# Example_Project.net
KiCad netlist of a schematic drawn in EAGLE
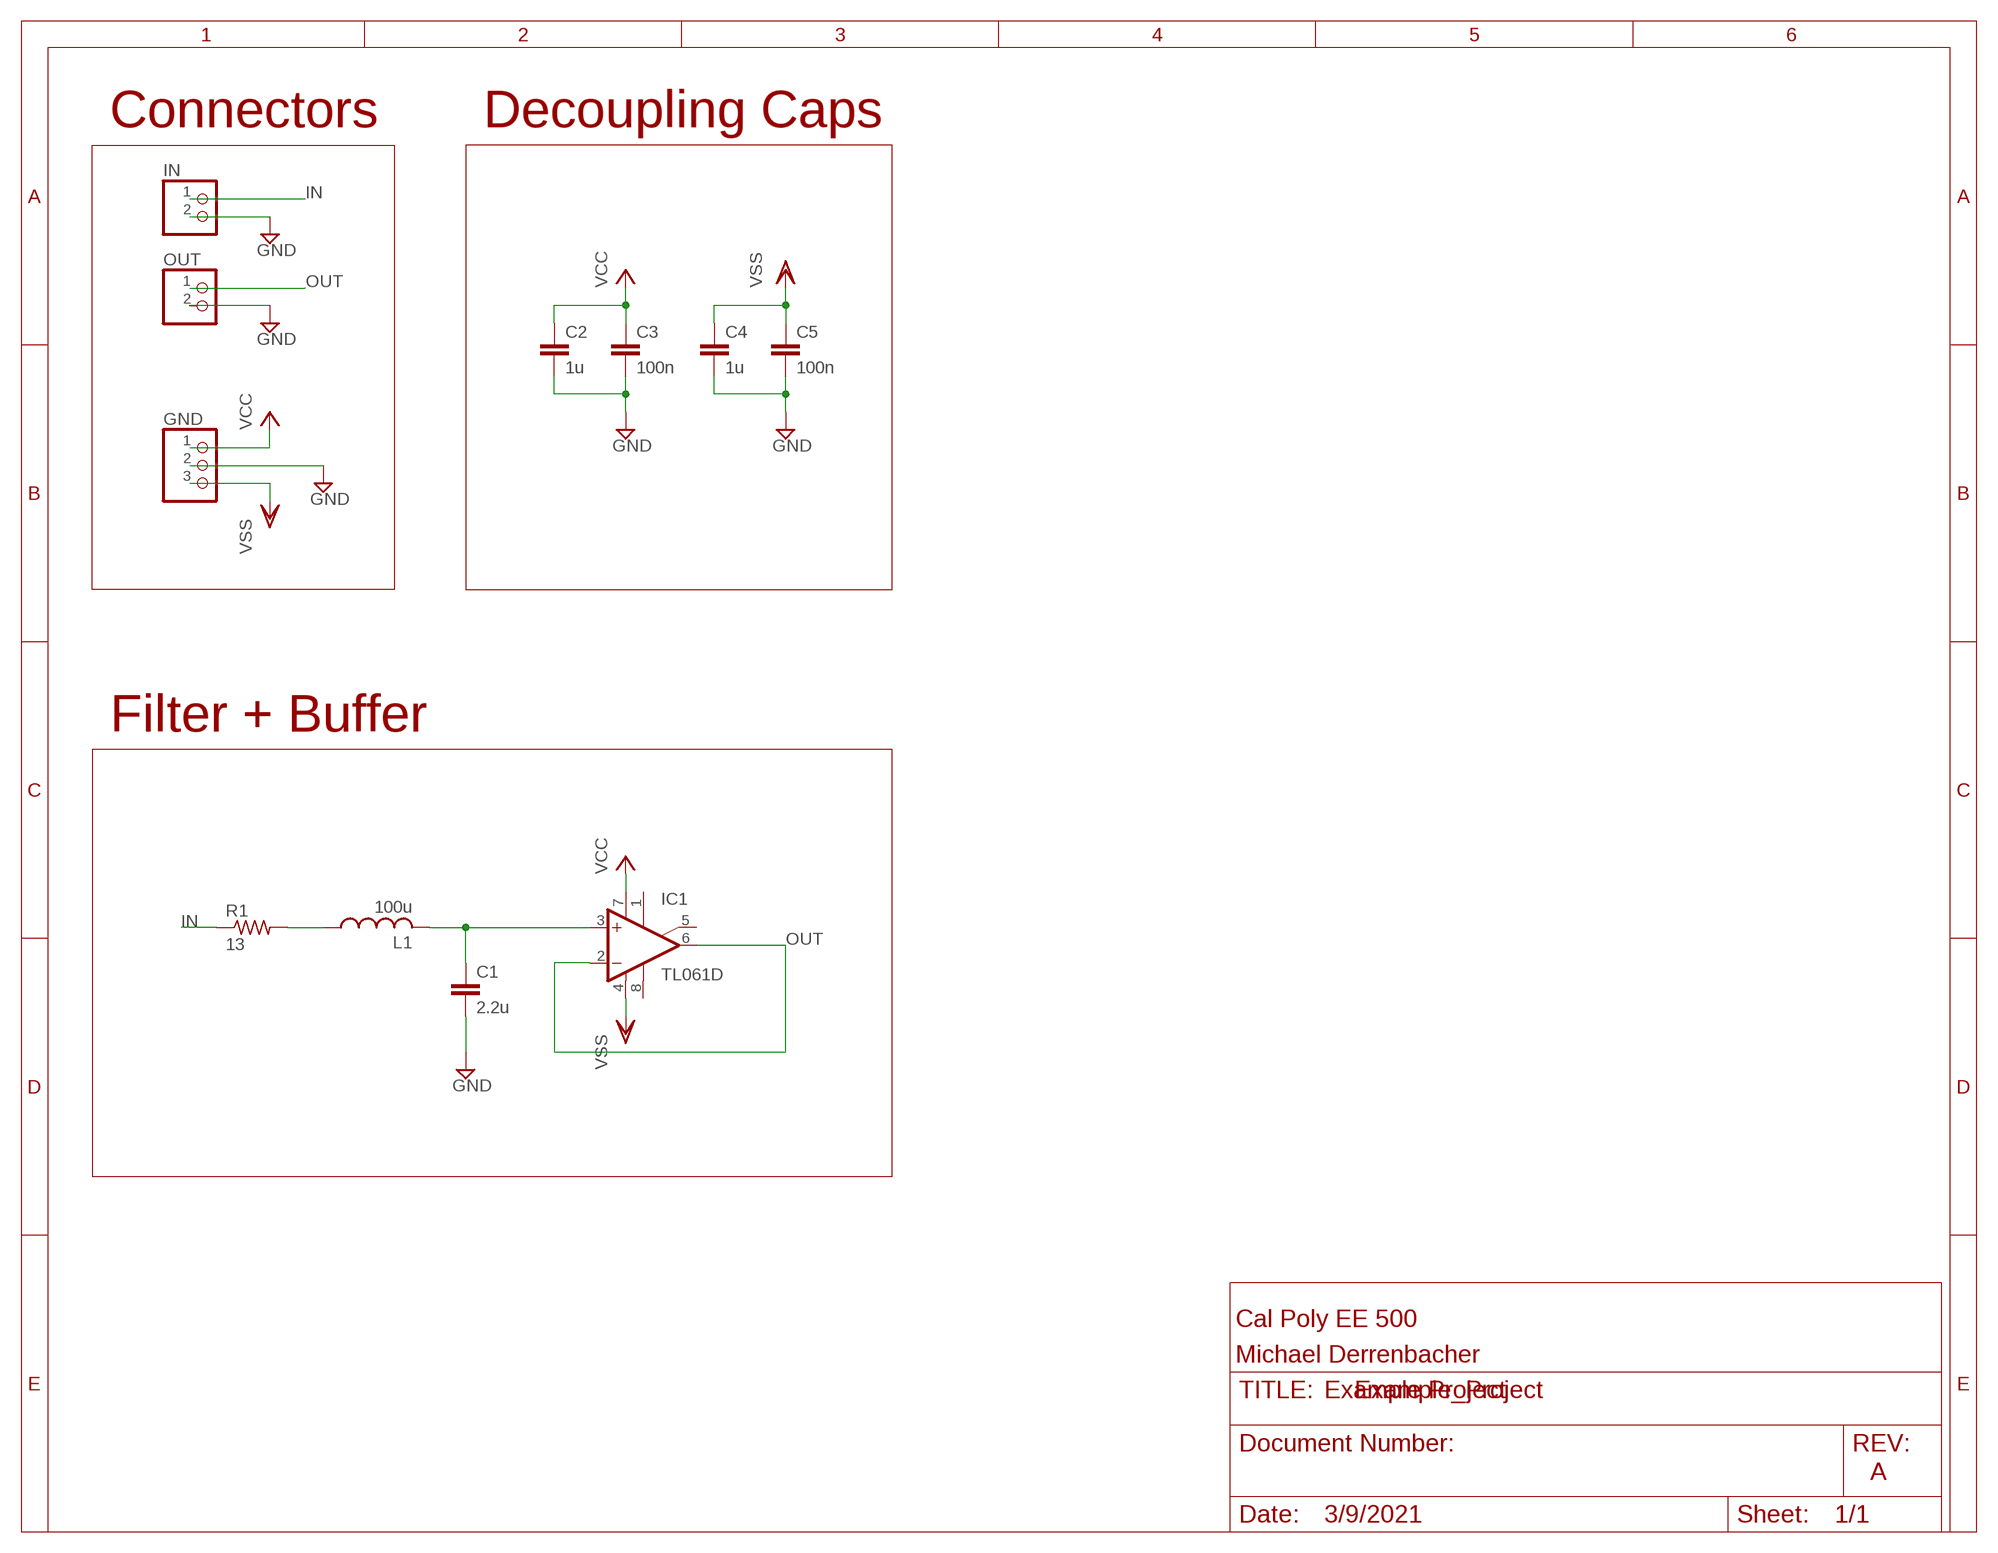
[diagram p0: schematic, sheet 1]

(export (version "E")
  (design (tool "Eeschema 10.0.6"))
  (components
    (comp (ref "C1")
      (value "2.2u")
      (footprint "eagle-import:C0805")
      (libsource (lib "eagle-import") (part "C-EUC0805"))
    )
    (comp (ref "C2")
      (value "1u")
      (footprint "eagle-import:C0805")
      (libsource (lib "eagle-import") (part "C-EUC0805"))
    )
    (comp (ref "C3")
      (value "100n")
      (footprint "eagle-import:C0805")
      (libsource (lib "eagle-import") (part "C-EUC0805"))
    )
    (comp (ref "C4")
      (value "1u")
      (footprint "eagle-import:C0805")
      (libsource (lib "eagle-import") (part "C-EUC0805"))
    )
    (comp (ref "C5")
      (value "100n")
      (footprint "eagle-import:C0805")
      (libsource (lib "eagle-import") (part "C-EUC0805"))
    )
    (comp (ref "GND")
      (value "PINHD-1X3")
      (footprint "eagle-import:1X03")
      (libsource (lib "eagle-import") (part "PINHD-1X3"))
    )
    (comp (ref "IC1")
      (value "TL061D")
      (footprint "eagle-import:SO08")
      (libsource (lib "eagle-import") (part "TL061D"))
    )
    (comp (ref "IN")
      (value "PINHD-1X2")
      (footprint "eagle-import:1X02")
      (libsource (lib "eagle-import") (part "PINHD-1X2"))
    )
    (comp (ref "L1")
      (value "100u")
      (footprint "eagle-import:L1812")
      (libsource (lib "eagle-import") (part "L-USL1812"))
    )
    (comp (ref "OUT")
      (value "PINHD-1X2")
      (footprint "eagle-import:1X02")
      (libsource (lib "eagle-import") (part "PINHD-1X2"))
    )
    (comp (ref "R1")
      (value "13")
      (footprint "eagle-import:R0805")
      (libsource (lib "eagle-import") (part "R-US_R0805"))
    )
  )
  (nets
    (net (code "1") (name "/IN") (class "Default")
      (node (ref "IN") (pin "1") (pinfunction "1_1") (pintype "passive"))
      (node (ref "R1") (pin "1") (pinfunction "1_1") (pintype "passive"))
    )
    (net (code "2") (name "/OUT") (class "Default")
      (node (ref "IC1") (pin "2") (pinfunction "-IN_2") (pintype "input"))
      (node (ref "IC1") (pin "6") (pinfunction "OUT_6") (pintype "output"))
      (node (ref "OUT") (pin "1") (pinfunction "1_1") (pintype "passive"))
    )
    (net (code "3") (name "GND") (class "Default")
      (node (ref "C1") (pin "2") (pinfunction "2_2") (pintype "passive"))
      (node (ref "C2") (pin "2") (pinfunction "2_2") (pintype "passive"))
      (node (ref "C3") (pin "2") (pinfunction "2_2") (pintype "passive"))
      (node (ref "C4") (pin "2") (pinfunction "2_2") (pintype "passive"))
      (node (ref "C5") (pin "2") (pinfunction "2_2") (pintype "passive"))
      (node (ref "GND") (pin "2") (pinfunction "2_2") (pintype "passive"))
      (node (ref "IN") (pin "2") (pinfunction "2_2") (pintype "passive"))
      (node (ref "OUT") (pin "2") (pinfunction "2_2") (pintype "passive"))
    )
    (net (code "4") (name "Net-(IC1-+IN)") (class "Default")
      (node (ref "C1") (pin "1") (pinfunction "1_1") (pintype "passive"))
      (node (ref "IC1") (pin "3") (pinfunction "+IN_3") (pintype "input"))
      (node (ref "L1") (pin "2") (pinfunction "2_2") (pintype "passive"))
    )
    (net (code "5") (name "Net-(L1-Pad1)") (class "Default")
      (node (ref "L1") (pin "1") (pinfunction "1_1") (pintype "passive"))
      (node (ref "R1") (pin "2") (pinfunction "2_2") (pintype "passive"))
    )
    (net (code "6") (name "VCC") (class "Default")
      (node (ref "C2") (pin "1") (pinfunction "1_1") (pintype "passive"))
      (node (ref "C3") (pin "1") (pinfunction "1_1") (pintype "passive"))
      (node (ref "GND") (pin "1") (pinfunction "1_1") (pintype "passive"))
      (node (ref "IC1") (pin "7") (pinfunction "V+_7") (pintype "power_in"))
    )
    (net (code "7") (name "VSS") (class "Default")
      (node (ref "C4") (pin "1") (pinfunction "1_1") (pintype "passive"))
      (node (ref "C5") (pin "1") (pinfunction "1_1") (pintype "passive"))
      (node (ref "GND") (pin "3") (pinfunction "3_3") (pintype "passive"))
      (node (ref "IC1") (pin "4") (pinfunction "V-_4") (pintype "power_in"))
    )
    (net (code "8") (name "unconnected-(IC1-ON1-Pad1)") (class "Default")
      (node (ref "IC1") (pin "1") (pinfunction "ON1_1") (pintype "passive"))
    )
    (net (code "9") (name "unconnected-(IC1-ON2-Pad5)") (class "Default")
      (node (ref "IC1") (pin "5") (pinfunction "ON2_5") (pintype "passive"))
    )
    (net (code "10") (name "unconnected-(IC1-OPT-Pad8)") (class "Default")
      (node (ref "IC1") (pin "8") (pinfunction "OPT_8") (pintype "passive"))
    )
  )
)
